# USBISPTiny.net
KiCad netlist of a schematic drawn in EAGLE
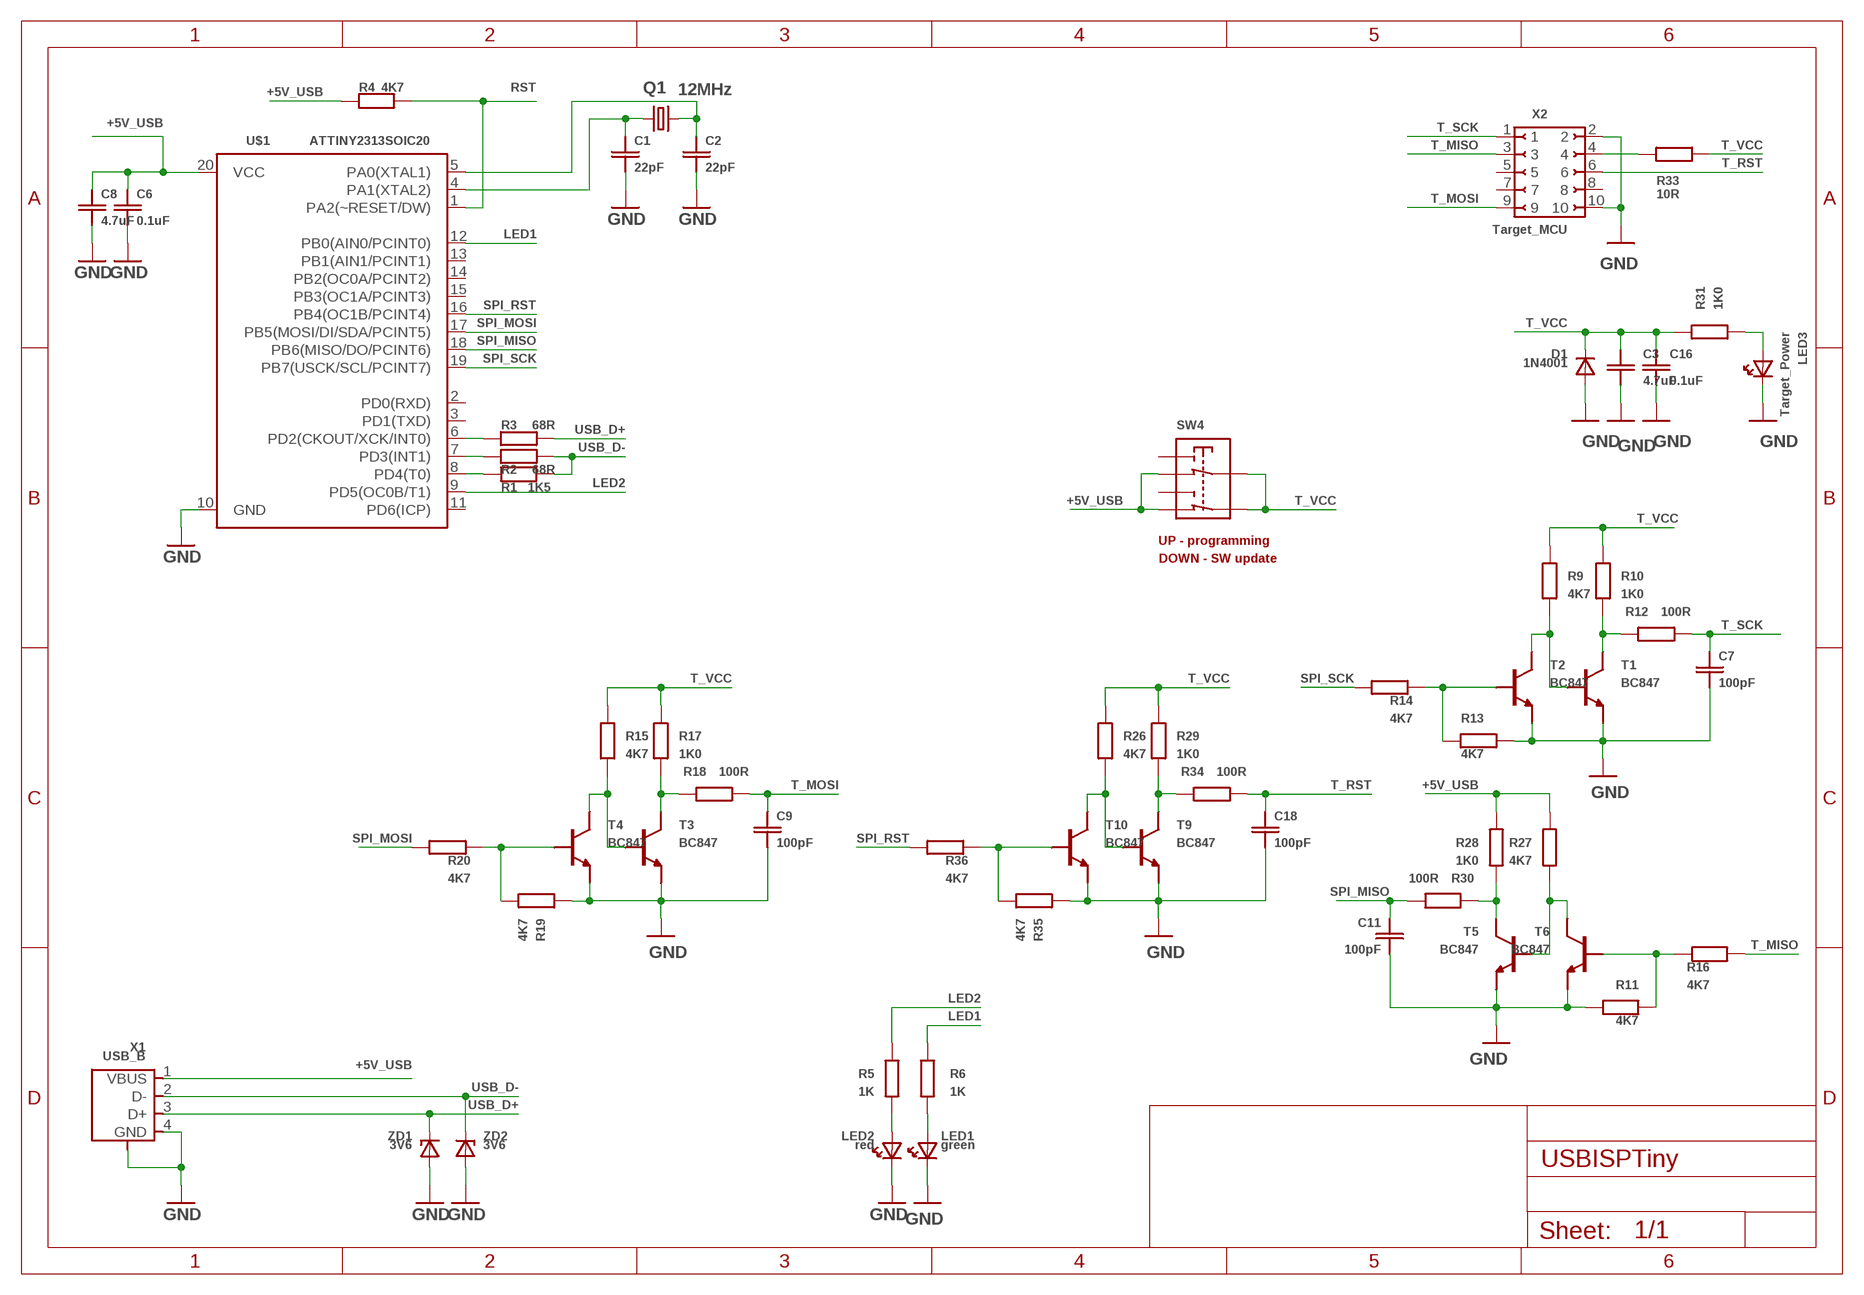
[diagram p0: schematic, sheet 1]

(export (version "E")
  (design (tool "Eeschema 10.0.6"))
  (components
    (comp (ref "C1")
      (value "22pF")
      (footprint "eagle-import:RSMD_0805")
      (libsource (lib "eagle-import") (part "CSMD_0805"))
    )
    (comp (ref "C2")
      (value "22pF")
      (footprint "eagle-import:RSMD_0805")
      (libsource (lib "eagle-import") (part "CSMD_0805"))
    )
    (comp (ref "C3")
      (value "4.7uF")
      (footprint "eagle-import:RSMD_1206")
      (libsource (lib "eagle-import") (part "CSMD_1206"))
    )
    (comp (ref "C6")
      (value "0.1uF")
      (footprint "eagle-import:RSMD_0805")
      (libsource (lib "eagle-import") (part "CSMD_0805"))
    )
    (comp (ref "C7")
      (value "100pF")
      (footprint "eagle-import:RSMD_0805")
      (libsource (lib "eagle-import") (part "CSMD_0805"))
    )
    (comp (ref "C8")
      (value "4.7uF")
      (footprint "eagle-import:RSMD_1206")
      (libsource (lib "eagle-import") (part "CSMD_1206"))
    )
    (comp (ref "C9")
      (value "100pF")
      (footprint "eagle-import:RSMD_0805")
      (libsource (lib "eagle-import") (part "CSMD_0805"))
    )
    (comp (ref "C11")
      (value "100pF")
      (footprint "eagle-import:RSMD_0805")
      (libsource (lib "eagle-import") (part "CSMD_0805"))
    )
    (comp (ref "C16")
      (value "0.1uF")
      (footprint "eagle-import:RSMD_0805")
      (libsource (lib "eagle-import") (part "CSMD_0805"))
    )
    (comp (ref "C18")
      (value "100pF")
      (footprint "eagle-import:RSMD_0805")
      (libsource (lib "eagle-import") (part "CSMD_0805"))
    )
    (comp (ref "D1")
      (value "1N4001")
      (footprint "eagle-import:DO-41_10MM")
      (libsource (lib "eagle-import") (part "1N4001DO-41_10MM"))
    )
    (comp (ref "LED1")
      (value "green")
      (footprint "eagle-import:LED3MM")
      (libsource (lib "eagle-import") (part "LED3MM"))
    )
    (comp (ref "LED2")
      (value "red")
      (footprint "eagle-import:LED3MM")
      (libsource (lib "eagle-import") (part "LED3MM"))
    )
    (comp (ref "LED3")
      (value "Target_Power")
      (footprint "eagle-import:LED3MM")
      (libsource (lib "eagle-import") (part "LED3MM"))
    )
    (comp (ref "Q1")
      (value "12MHz")
      (footprint "eagle-import:HC49U-V")
      (libsource (lib "eagle-import") (part "CRYSTALHC49U-V"))
    )
    (comp (ref "R1")
      (value "1K5")
      (footprint "eagle-import:RSMD_0805")
      (libsource (lib "eagle-import") (part "RSMD_0805"))
    )
    (comp (ref "R2")
      (value "68R")
      (footprint "eagle-import:RSMD_0805")
      (libsource (lib "eagle-import") (part "RSMD_0805"))
    )
    (comp (ref "R3")
      (value "68R")
      (footprint "eagle-import:RSMD_0805")
      (libsource (lib "eagle-import") (part "RSMD_0805"))
    )
    (comp (ref "R4")
      (value "4K7")
      (footprint "eagle-import:RSMD_1206")
      (libsource (lib "eagle-import") (part "RSMD_1206"))
    )
    (comp (ref "R5")
      (value "1K")
      (footprint "eagle-import:RSMD_0805")
      (libsource (lib "eagle-import") (part "RSMD_0805"))
    )
    (comp (ref "R6")
      (value "1K")
      (footprint "eagle-import:RSMD_0805")
      (libsource (lib "eagle-import") (part "RSMD_0805"))
    )
    (comp (ref "R9")
      (value "4K7")
      (footprint "eagle-import:RSMD_0805")
      (libsource (lib "eagle-import") (part "RSMD_0805"))
    )
    (comp (ref "R10")
      (value "1K0")
      (footprint "eagle-import:RSMD_0805")
      (libsource (lib "eagle-import") (part "RSMD_0805"))
    )
    (comp (ref "R11")
      (value "4K7")
      (footprint "eagle-import:RSMD_0805")
      (libsource (lib "eagle-import") (part "RSMD_0805"))
    )
    (comp (ref "R12")
      (value "100R")
      (footprint "eagle-import:R0204")
      (libsource (lib "eagle-import") (part "R0204"))
    )
    (comp (ref "R13")
      (value "4K7")
      (footprint "eagle-import:RSMD_0805")
      (libsource (lib "eagle-import") (part "RSMD_0805"))
    )
    (comp (ref "R14")
      (value "4K7")
      (footprint "eagle-import:RSMD_0805")
      (libsource (lib "eagle-import") (part "RSMD_0805"))
    )
    (comp (ref "R15")
      (value "4K7")
      (footprint "eagle-import:RSMD_0805")
      (libsource (lib "eagle-import") (part "RSMD_0805"))
    )
    (comp (ref "R16")
      (value "4K7")
      (footprint "eagle-import:R0207")
      (libsource (lib "eagle-import") (part "R0207"))
    )
    (comp (ref "R17")
      (value "1K0")
      (footprint "eagle-import:RSMD_0805")
      (libsource (lib "eagle-import") (part "RSMD_0805"))
    )
    (comp (ref "R18")
      (value "100R")
      (footprint "eagle-import:R0204")
      (libsource (lib "eagle-import") (part "R0204"))
    )
    (comp (ref "R19")
      (value "4K7")
      (footprint "eagle-import:RSMD_0805")
      (libsource (lib "eagle-import") (part "RSMD_0805"))
    )
    (comp (ref "R20")
      (value "4K7")
      (footprint "eagle-import:RSMD_0805")
      (libsource (lib "eagle-import") (part "RSMD_0805"))
    )
    (comp (ref "R26")
      (value "4K7")
      (footprint "eagle-import:RSMD_0805")
      (libsource (lib "eagle-import") (part "RSMD_0805"))
    )
    (comp (ref "R27")
      (value "4K7")
      (footprint "eagle-import:RSMD_0805")
      (libsource (lib "eagle-import") (part "RSMD_0805"))
    )
    (comp (ref "R28")
      (value "1K0")
      (footprint "eagle-import:RSMD_0805")
      (libsource (lib "eagle-import") (part "RSMD_0805"))
    )
    (comp (ref "R29")
      (value "1K0")
      (footprint "eagle-import:RSMD_0805")
      (libsource (lib "eagle-import") (part "RSMD_0805"))
    )
    (comp (ref "R30")
      (value "100R")
      (footprint "eagle-import:RSMD_0805")
      (libsource (lib "eagle-import") (part "RSMD_0805"))
    )
    (comp (ref "R31")
      (value "1K0")
      (footprint "eagle-import:RSMD_0805")
      (libsource (lib "eagle-import") (part "RSMD_0805"))
    )
    (comp (ref "R33")
      (value "10R")
      (footprint "eagle-import:R0204")
      (libsource (lib "eagle-import") (part "R0204"))
    )
    (comp (ref "R34")
      (value "100R")
      (footprint "eagle-import:R0207")
      (libsource (lib "eagle-import") (part "R0207"))
    )
    (comp (ref "R35")
      (value "4K7")
      (footprint "eagle-import:RSMD_0805")
      (libsource (lib "eagle-import") (part "RSMD_0805"))
    )
    (comp (ref "R36")
      (value "4K7")
      (footprint "eagle-import:RSMD_0805")
      (libsource (lib "eagle-import") (part "RSMD_0805"))
    )
    (comp (ref "SW4")
      (value "SWITCH_DOUBLE(2.54X4MM)")
      (footprint "eagle-import:SWITCH_DOUBLE_2.54X4.0MM")
      (libsource (lib "eagle-import") (part "SWITCH_DOUBLE(2.54X4MM)"))
    )
    (comp (ref "T1")
      (value "BC847")
      (footprint "eagle-import:SOT23_SMALL_PADS")
      (libsource (lib "eagle-import") (part "BC847SOT23_SMALL_PADS"))
    )
    (comp (ref "T2")
      (value "BC847")
      (footprint "eagle-import:SOT23_SMALL_PADS")
      (libsource (lib "eagle-import") (part "BC847SOT23_SMALL_PADS"))
    )
    (comp (ref "T3")
      (value "BC847")
      (footprint "eagle-import:SOT23_SMALL_PADS")
      (libsource (lib "eagle-import") (part "BC847SOT23_SMALL_PADS"))
    )
    (comp (ref "T4")
      (value "BC847")
      (footprint "eagle-import:SOT23_SMALL_PADS")
      (libsource (lib "eagle-import") (part "BC847SOT23_SMALL_PADS"))
    )
    (comp (ref "T5")
      (value "BC847")
      (footprint "eagle-import:SOT23_SMALL_PADS")
      (libsource (lib "eagle-import") (part "BC847SOT23_SMALL_PADS"))
    )
    (comp (ref "T6")
      (value "BC847")
      (footprint "eagle-import:SOT23_SMALL_PADS")
      (libsource (lib "eagle-import") (part "BC847SOT23_SMALL_PADS"))
    )
    (comp (ref "T9")
      (value "BC847")
      (footprint "eagle-import:SOT23_SMALL_PADS")
      (libsource (lib "eagle-import") (part "BC847SOT23_SMALL_PADS"))
    )
    (comp (ref "T10")
      (value "BC847")
      (footprint "eagle-import:SOT23_SMALL_PADS")
      (libsource (lib "eagle-import") (part "BC847SOT23_SMALL_PADS"))
    )
    (comp (ref "U$1")
      (value "ATTINY2313SOIC20")
      (footprint "eagle-import:SOIC20")
      (libsource (lib "eagle-import") (part "ATTINY2313SOIC20"))
    )
    (comp (ref "X1")
      (value "USB_B")
      (footprint "eagle-import:USB_TYPE_B_SMALL_PADS")
      (libsource (lib "eagle-import") (part "USB_TYPE_B(TYPE_B_SMALL_PADS)"))
    )
    (comp (ref "X2")
      (value "Target_MCU")
      (footprint "eagle-import:PIN2X5_2.54MM_FEMALE_RIGHT_ANGLE_SMALL_PADS")
      (libsource (lib "eagle-import") (part "PIN2X5_FEMALE2.54MM_RIGHT_ANGLE_SMALL_PADS"))
    )
    (comp (ref "ZD1")
      (value "3V6")
      (footprint "eagle-import:SOD-80")
      (libsource (lib "eagle-import") (part "ZENNER(SOD_80)"))
    )
    (comp (ref "ZD2")
      (value "3V6")
      (footprint "eagle-import:SOD-80")
      (libsource (lib "eagle-import") (part "ZENNER(SOD_80)"))
    )
  )
  (nets
    (net (code "1") (name "/+5V_USB") (class "Default")
      (node (ref "C6") (pin "PAD_1") (pinfunction "PIN1_PAD_1") (pintype "bidirectional"))
      (node (ref "C8") (pin "PAD_1") (pinfunction "PIN1_PAD_1") (pintype "bidirectional"))
      (node (ref "R27") (pin "PAD_0") (pinfunction "PIN0_PAD_0") (pintype "passive"))
      (node (ref "R28") (pin "PAD_0") (pinfunction "PIN0_PAD_0") (pintype "passive"))
      (node (ref "R4") (pin "PAD_0") (pinfunction "PIN0_PAD_0") (pintype "passive"))
      (node (ref "SW4") (pin "POS_B1") (pinfunction "POS_B1_POS_B1") (pintype "bidirectional"))
      (node (ref "SW4") (pin "POS_B2") (pinfunction "POS_B2_POS_B2") (pintype "bidirectional"))
      (node (ref "U$1") (pin "20") (pinfunction "VCC_20") (pintype "bidirectional"))
      (node (ref "X1") (pin "1") (pinfunction "VBUS_1") (pintype "bidirectional"))
    )
    (net (code "2") (name "/LED1") (class "Default")
      (node (ref "R6") (pin "PAD_0") (pinfunction "PIN0_PAD_0") (pintype "passive"))
      (node (ref "U$1") (pin "12") (pinfunction "PB0(AIN0/PCINT0)_12") (pintype "bidirectional"))
    )
    (net (code "3") (name "/LED2") (class "Default")
      (node (ref "R5") (pin "PAD_0") (pinfunction "PIN0_PAD_0") (pintype "passive"))
      (node (ref "U$1") (pin "9") (pinfunction "PD5(OC0B/T1)_9") (pintype "bidirectional"))
    )
    (net (code "4") (name "/RST") (class "Default")
      (node (ref "R4") (pin "PAD_1") (pinfunction "PIN1_PAD_1") (pintype "passive"))
      (node (ref "U$1") (pin "1") (pinfunction "PA2(~{RESET/DW})_1") (pintype "bidirectional"))
    )
    (net (code "5") (name "/SPI_MISO") (class "Default")
      (node (ref "C11") (pin "PAD_1") (pinfunction "PIN1_PAD_1") (pintype "bidirectional"))
      (node (ref "R30") (pin "PAD_1") (pinfunction "PIN1_PAD_1") (pintype "passive"))
      (node (ref "U$1") (pin "18") (pinfunction "PB6(MISO/DO/PCINT6)_18") (pintype "bidirectional"))
    )
    (net (code "6") (name "/SPI_MOSI") (class "Default")
      (node (ref "R20") (pin "PAD_1") (pinfunction "PIN1_PAD_1") (pintype "passive"))
      (node (ref "U$1") (pin "17") (pinfunction "PB5(MOSI/DI/SDA/PCINT5)_17") (pintype "bidirectional"))
    )
    (net (code "7") (name "/SPI_RST") (class "Default")
      (node (ref "R36") (pin "PAD_1") (pinfunction "PIN1_PAD_1") (pintype "passive"))
      (node (ref "U$1") (pin "16") (pinfunction "PB4(OC1B/PCINT4)_16") (pintype "bidirectional"))
    )
    (net (code "8") (name "/SPI_SCK") (class "Default")
      (node (ref "R14") (pin "PAD_1") (pinfunction "PIN1_PAD_1") (pintype "passive"))
      (node (ref "U$1") (pin "19") (pinfunction "PB7(USCK/SCL/PCINT7)_19") (pintype "bidirectional"))
    )
    (net (code "9") (name "/T_MISO") (class "Default")
      (node (ref "R16") (pin "PAD1") (pinfunction "PIN1_PAD1") (pintype "passive"))
      (node (ref "X2") (pin "3") (pinfunction "3_3") (pintype "bidirectional"))
    )
    (net (code "10") (name "/T_MOSI") (class "Default")
      (node (ref "C9") (pin "PAD_1") (pinfunction "PIN1_PAD_1") (pintype "bidirectional"))
      (node (ref "R18") (pin "PAD1") (pinfunction "PIN1_PAD1") (pintype "passive"))
      (node (ref "X2") (pin "9") (pinfunction "9_9") (pintype "bidirectional"))
    )
    (net (code "11") (name "/T_RST") (class "Default")
      (node (ref "C18") (pin "PAD_1") (pinfunction "PIN1_PAD_1") (pintype "bidirectional"))
      (node (ref "R34") (pin "PAD1") (pinfunction "PIN1_PAD1") (pintype "passive"))
      (node (ref "X2") (pin "6") (pinfunction "6_6") (pintype "bidirectional"))
    )
    (net (code "12") (name "/T_SCK") (class "Default")
      (node (ref "C7") (pin "PAD_1") (pinfunction "PIN1_PAD_1") (pintype "bidirectional"))
      (node (ref "R12") (pin "PAD1") (pinfunction "PIN1_PAD1") (pintype "passive"))
      (node (ref "X2") (pin "1") (pinfunction "1_1") (pintype "bidirectional"))
    )
    (net (code "13") (name "/T_VCC") (class "Default")
      (node (ref "C16") (pin "PAD_1") (pinfunction "PIN1_PAD_1") (pintype "bidirectional"))
      (node (ref "C3") (pin "PAD_1") (pinfunction "PIN1_PAD_1") (pintype "bidirectional"))
      (node (ref "D1") (pin "CATHODE") (pinfunction "CATHODE_CATHODE") (pintype "passive"))
      (node (ref "R10") (pin "PAD_0") (pinfunction "PIN0_PAD_0") (pintype "passive"))
      (node (ref "R15") (pin "PAD_0") (pinfunction "PIN0_PAD_0") (pintype "passive"))
      (node (ref "R17") (pin "PAD_0") (pinfunction "PIN0_PAD_0") (pintype "passive"))
      (node (ref "R26") (pin "PAD_0") (pinfunction "PIN0_PAD_0") (pintype "passive"))
      (node (ref "R29") (pin "PAD_0") (pinfunction "PIN0_PAD_0") (pintype "passive"))
      (node (ref "R31") (pin "PAD_0") (pinfunction "PIN0_PAD_0") (pintype "passive"))
      (node (ref "R33") (pin "PAD_0") (pinfunction "PIN0_PAD_0") (pintype "passive"))
      (node (ref "R9") (pin "PAD_0") (pinfunction "PIN0_PAD_0") (pintype "passive"))
      (node (ref "SW4") (pin "CENTER1") (pinfunction "CENTER1_CENTER1") (pintype "bidirectional"))
      (node (ref "SW4") (pin "CENTER2") (pinfunction "CENTER2_CENTER2") (pintype "bidirectional"))
    )
    (net (code "14") (name "/USB_D+") (class "Default")
      (node (ref "R3") (pin "PAD_1") (pinfunction "PIN1_PAD_1") (pintype "passive"))
      (node (ref "X1") (pin "3") (pinfunction "D+_3") (pintype "bidirectional"))
      (node (ref "ZD1") (pin "CATHODE") (pinfunction "CATHODE_CATHODE") (pintype "passive"))
    )
    (net (code "15") (name "/USB_D-") (class "Default")
      (node (ref "R1") (pin "PAD_0") (pinfunction "PIN0_PAD_0") (pintype "passive"))
      (node (ref "R2") (pin "PAD_0") (pinfunction "PIN0_PAD_0") (pintype "passive"))
      (node (ref "X1") (pin "2") (pinfunction "D-_2") (pintype "bidirectional"))
      (node (ref "ZD2") (pin "CATHODE") (pinfunction "CATHODE_CATHODE") (pintype "passive"))
    )
    (net (code "16") (name "GND") (class "Default")
      (node (ref "C1") (pin "PAD_0") (pinfunction "PIN0_PAD_0") (pintype "bidirectional"))
      (node (ref "C11") (pin "PAD_0") (pinfunction "PIN0_PAD_0") (pintype "bidirectional"))
      (node (ref "C16") (pin "PAD_0") (pinfunction "PIN0_PAD_0") (pintype "bidirectional"))
      (node (ref "C18") (pin "PAD_0") (pinfunction "PIN0_PAD_0") (pintype "bidirectional"))
      (node (ref "C2") (pin "PAD_0") (pinfunction "PIN0_PAD_0") (pintype "bidirectional"))
      (node (ref "C3") (pin "PAD_0") (pinfunction "PIN0_PAD_0") (pintype "bidirectional"))
      (node (ref "C6") (pin "PAD_0") (pinfunction "PIN0_PAD_0") (pintype "bidirectional"))
      (node (ref "C7") (pin "PAD_0") (pinfunction "PIN0_PAD_0") (pintype "bidirectional"))
      (node (ref "C8") (pin "PAD_0") (pinfunction "PIN0_PAD_0") (pintype "bidirectional"))
      (node (ref "C9") (pin "PAD_0") (pinfunction "PIN0_PAD_0") (pintype "bidirectional"))
      (node (ref "D1") (pin "ANODE") (pinfunction "ANODE_ANODE") (pintype "passive"))
      (node (ref "LED1") (pin "CATHODE") (pinfunction "CATHODE_CATHODE") (pintype "passive"))
      (node (ref "LED2") (pin "CATHODE") (pinfunction "CATHODE_CATHODE") (pintype "passive"))
      (node (ref "LED3") (pin "CATHODE") (pinfunction "CATHODE_CATHODE") (pintype "passive"))
      (node (ref "R11") (pin "PAD_0") (pinfunction "PIN0_PAD_0") (pintype "passive"))
      (node (ref "R13") (pin "PAD_0") (pinfunction "PIN0_PAD_0") (pintype "passive"))
      (node (ref "R19") (pin "PAD_0") (pinfunction "PIN0_PAD_0") (pintype "passive"))
      (node (ref "R35") (pin "PAD_0") (pinfunction "PIN0_PAD_0") (pintype "passive"))
      (node (ref "T1") (pin "2") (pinfunction "E_2") (pintype "bidirectional"))
      (node (ref "T10") (pin "2") (pinfunction "E_2") (pintype "bidirectional"))
      (node (ref "T2") (pin "2") (pinfunction "E_2") (pintype "bidirectional"))
      (node (ref "T3") (pin "2") (pinfunction "E_2") (pintype "bidirectional"))
      (node (ref "T4") (pin "2") (pinfunction "E_2") (pintype "bidirectional"))
      (node (ref "T5") (pin "2") (pinfunction "E_2") (pintype "bidirectional"))
      (node (ref "T6") (pin "2") (pinfunction "E_2") (pintype "bidirectional"))
      (node (ref "T9") (pin "2") (pinfunction "E_2") (pintype "bidirectional"))
      (node (ref "U$1") (pin "10") (pinfunction "GND_10") (pintype "bidirectional"))
      (node (ref "X1") (pin "4") (pinfunction "GND_4") (pintype "bidirectional"))
      (node (ref "X1") (pin "PACKAGE_PAD1") (pinfunction "PACKAGE_PACKAGE_PAD1") (pintype "bidirectional"))
      (node (ref "X1") (pin "PACKAGE_PAD2") (pinfunction "PACKAGE_PACKAGE_PAD2") (pintype "bidirectional"))
      (node (ref "X2") (pin "10") (pinfunction "10_10") (pintype "bidirectional"))
      (node (ref "X2") (pin "2") (pinfunction "2_2") (pintype "bidirectional"))
      (node (ref "ZD1") (pin "ANODE") (pinfunction "ANODE_ANODE") (pintype "passive"))
      (node (ref "ZD2") (pin "ANODE") (pinfunction "ANODE_ANODE") (pintype "passive"))
    )
    (net (code "17") (name "Net-(C1-PIN1)") (class "Default")
      (node (ref "C1") (pin "PAD_1") (pinfunction "PIN1_PAD_1") (pintype "bidirectional"))
      (node (ref "Q1") (pin "1") (pinfunction "1_1") (pintype "passive"))
      (node (ref "U$1") (pin "4") (pinfunction "PA1(XTAL2)_4") (pintype "bidirectional"))
    )
    (net (code "18") (name "Net-(C2-PIN1)") (class "Default")
      (node (ref "C2") (pin "PAD_1") (pinfunction "PIN1_PAD_1") (pintype "bidirectional"))
      (node (ref "Q1") (pin "2") (pinfunction "2_2") (pintype "passive"))
      (node (ref "U$1") (pin "5") (pinfunction "PA0(XTAL1)_5") (pintype "bidirectional"))
    )
    (net (code "19") (name "Net-(R1-PIN1)") (class "Default")
      (node (ref "R1") (pin "PAD_1") (pinfunction "PIN1_PAD_1") (pintype "passive"))
      (node (ref "U$1") (pin "8") (pinfunction "PD4(T0)_8") (pintype "bidirectional"))
    )
    (net (code "20") (name "Net-(R2-PIN1)") (class "Default")
      (node (ref "R2") (pin "PAD_1") (pinfunction "PIN1_PAD_1") (pintype "passive"))
      (node (ref "U$1") (pin "7") (pinfunction "PD3(INT1)_7") (pintype "bidirectional"))
    )
    (net (code "21") (name "Net-(R3-PIN0)") (class "Default")
      (node (ref "R3") (pin "PAD_0") (pinfunction "PIN0_PAD_0") (pintype "passive"))
      (node (ref "U$1") (pin "6") (pinfunction "PD2(CKOUT/XCK/INT0)_6") (pintype "bidirectional"))
    )
    (net (code "22") (name "Net-(R5-PIN1)") (class "Default")
      (node (ref "LED2") (pin "ANODE") (pinfunction "ANODE_ANODE") (pintype "passive"))
      (node (ref "R5") (pin "PAD_1") (pinfunction "PIN1_PAD_1") (pintype "passive"))
    )
    (net (code "23") (name "Net-(R6-PIN1)") (class "Default")
      (node (ref "LED1") (pin "ANODE") (pinfunction "ANODE_ANODE") (pintype "passive"))
      (node (ref "R6") (pin "PAD_1") (pinfunction "PIN1_PAD_1") (pintype "passive"))
    )
    (net (code "24") (name "Net-(R9-PIN1)") (class "Default")
      (node (ref "R9") (pin "PAD_1") (pinfunction "PIN1_PAD_1") (pintype "passive"))
      (node (ref "T1") (pin "1") (pinfunction "B_1") (pintype "bidirectional"))
      (node (ref "T2") (pin "3") (pinfunction "C_3") (pintype "bidirectional"))
    )
    (net (code "25") (name "Net-(R10-PIN1)") (class "Default")
      (node (ref "R10") (pin "PAD_1") (pinfunction "PIN1_PAD_1") (pintype "passive"))
      (node (ref "R12") (pin "PAD_0") (pinfunction "PIN0_PAD_0") (pintype "passive"))
      (node (ref "T1") (pin "3") (pinfunction "C_3") (pintype "bidirectional"))
    )
    (net (code "26") (name "Net-(R11-PIN1)") (class "Default")
      (node (ref "R11") (pin "PAD_1") (pinfunction "PIN1_PAD_1") (pintype "passive"))
      (node (ref "R16") (pin "PAD_0") (pinfunction "PIN0_PAD_0") (pintype "passive"))
      (node (ref "T6") (pin "1") (pinfunction "B_1") (pintype "bidirectional"))
    )
    (net (code "27") (name "Net-(R13-PIN1)") (class "Default")
      (node (ref "R13") (pin "PAD_1") (pinfunction "PIN1_PAD_1") (pintype "passive"))
      (node (ref "R14") (pin "PAD_0") (pinfunction "PIN0_PAD_0") (pintype "passive"))
      (node (ref "T2") (pin "1") (pinfunction "B_1") (pintype "bidirectional"))
    )
    (net (code "28") (name "Net-(R15-PIN1)") (class "Default")
      (node (ref "R15") (pin "PAD_1") (pinfunction "PIN1_PAD_1") (pintype "passive"))
      (node (ref "T3") (pin "1") (pinfunction "B_1") (pintype "bidirectional"))
      (node (ref "T4") (pin "3") (pinfunction "C_3") (pintype "bidirectional"))
    )
    (net (code "29") (name "Net-(R17-PIN1)") (class "Default")
      (node (ref "R17") (pin "PAD_1") (pinfunction "PIN1_PAD_1") (pintype "passive"))
      (node (ref "R18") (pin "PAD_0") (pinfunction "PIN0_PAD_0") (pintype "passive"))
      (node (ref "T3") (pin "3") (pinfunction "C_3") (pintype "bidirectional"))
    )
    (net (code "30") (name "Net-(R19-PIN1)") (class "Default")
      (node (ref "R19") (pin "PAD_1") (pinfunction "PIN1_PAD_1") (pintype "passive"))
      (node (ref "R20") (pin "PAD_0") (pinfunction "PIN0_PAD_0") (pintype "passive"))
      (node (ref "T4") (pin "1") (pinfunction "B_1") (pintype "bidirectional"))
    )
    (net (code "31") (name "Net-(R26-PIN1)") (class "Default")
      (node (ref "R26") (pin "PAD_1") (pinfunction "PIN1_PAD_1") (pintype "passive"))
      (node (ref "T10") (pin "3") (pinfunction "C_3") (pintype "bidirectional"))
      (node (ref "T9") (pin "1") (pinfunction "B_1") (pintype "bidirectional"))
    )
    (net (code "32") (name "Net-(R27-PIN1)") (class "Default")
      (node (ref "R27") (pin "PAD_1") (pinfunction "PIN1_PAD_1") (pintype "passive"))
      (node (ref "T5") (pin "1") (pinfunction "B_1") (pintype "bidirectional"))
      (node (ref "T6") (pin "3") (pinfunction "C_3") (pintype "bidirectional"))
    )
    (net (code "33") (name "Net-(R28-PIN1)") (class "Default")
      (node (ref "R28") (pin "PAD_1") (pinfunction "PIN1_PAD_1") (pintype "passive"))
      (node (ref "R30") (pin "PAD_0") (pinfunction "PIN0_PAD_0") (pintype "passive"))
      (node (ref "T5") (pin "3") (pinfunction "C_3") (pintype "bidirectional"))
    )
    (net (code "34") (name "Net-(R29-PIN1)") (class "Default")
      (node (ref "R29") (pin "PAD_1") (pinfunction "PIN1_PAD_1") (pintype "passive"))
      (node (ref "R34") (pin "PAD_0") (pinfunction "PIN0_PAD_0") (pintype "passive"))
      (node (ref "T9") (pin "3") (pinfunction "C_3") (pintype "bidirectional"))
    )
    (net (code "35") (name "Net-(R31-PIN1)") (class "Default")
      (node (ref "LED3") (pin "ANODE") (pinfunction "ANODE_ANODE") (pintype "passive"))
      (node (ref "R31") (pin "PAD_1") (pinfunction "PIN1_PAD_1") (pintype "passive"))
    )
    (net (code "36") (name "Net-(R33-PIN1)") (class "Default")
      (node (ref "R33") (pin "PAD1") (pinfunction "PIN1_PAD1") (pintype "passive"))
      (node (ref "X2") (pin "4") (pinfunction "4_4") (pintype "bidirectional"))
    )
    (net (code "37") (name "Net-(R35-PIN1)") (class "Default")
      (node (ref "R35") (pin "PAD_1") (pinfunction "PIN1_PAD_1") (pintype "passive"))
      (node (ref "R36") (pin "PAD_0") (pinfunction "PIN0_PAD_0") (pintype "passive"))
      (node (ref "T10") (pin "1") (pinfunction "B_1") (pintype "bidirectional"))
    )
    (net (code "38") (name "unconnected-(SW4-PadPOS_A1)") (class "Default")
      (node (ref "SW4") (pin "POS_A1") (pinfunction "POS_A1_POS_A1") (pintype "bidirectional"))
    )
    (net (code "39") (name "unconnected-(SW4-PadPOS_A2)") (class "Default")
      (node (ref "SW4") (pin "POS_A2") (pinfunction "POS_A2_POS_A2") (pintype "bidirectional"))
    )
    (net (code "40") (name "unconnected-(U$1-PB1(AIN1{slash}PCINT1)-Pad13)") (class "Default")
      (node (ref "U$1") (pin "13") (pinfunction "PB1(AIN1/PCINT1)_13") (pintype "bidirectional"))
    )
    (net (code "41") (name "unconnected-(U$1-PB2(OC0A{slash}PCINT2)-Pad14)") (class "Default")
      (node (ref "U$1") (pin "14") (pinfunction "PB2(OC0A/PCINT2)_14") (pintype "bidirectional"))
    )
    (net (code "42") (name "unconnected-(U$1-PB3(OC1A{slash}PCINT3)-Pad15)") (class "Default")
      (node (ref "U$1") (pin "15") (pinfunction "PB3(OC1A/PCINT3)_15") (pintype "bidirectional"))
    )
    (net (code "43") (name "unconnected-(U$1-PD0(RXD)-Pad2)") (class "Default")
      (node (ref "U$1") (pin "2") (pinfunction "PD0(RXD)_2") (pintype "bidirectional"))
    )
    (net (code "44") (name "unconnected-(U$1-PD1(TXD)-Pad3)") (class "Default")
      (node (ref "U$1") (pin "3") (pinfunction "PD1(TXD)_3") (pintype "bidirectional"))
    )
    (net (code "45") (name "unconnected-(U$1-PD6(ICP)-Pad11)") (class "Default")
      (node (ref "U$1") (pin "11") (pinfunction "PD6(ICP)_11") (pintype "bidirectional"))
    )
    (net (code "46") (name "unconnected-(X2-Pad5)") (class "Default")
      (node (ref "X2") (pin "5") (pinfunction "5_5") (pintype "bidirectional"))
    )
    (net (code "47") (name "unconnected-(X2-Pad7)") (class "Default")
      (node (ref "X2") (pin "7") (pinfunction "7_7") (pintype "bidirectional"))
    )
    (net (code "48") (name "unconnected-(X2-Pad8)") (class "Default")
      (node (ref "X2") (pin "8") (pinfunction "8_8") (pintype "bidirectional"))
    )
  )
)
